# power_input.net
KiCad netlist of a schematic drawn in Altium Designer
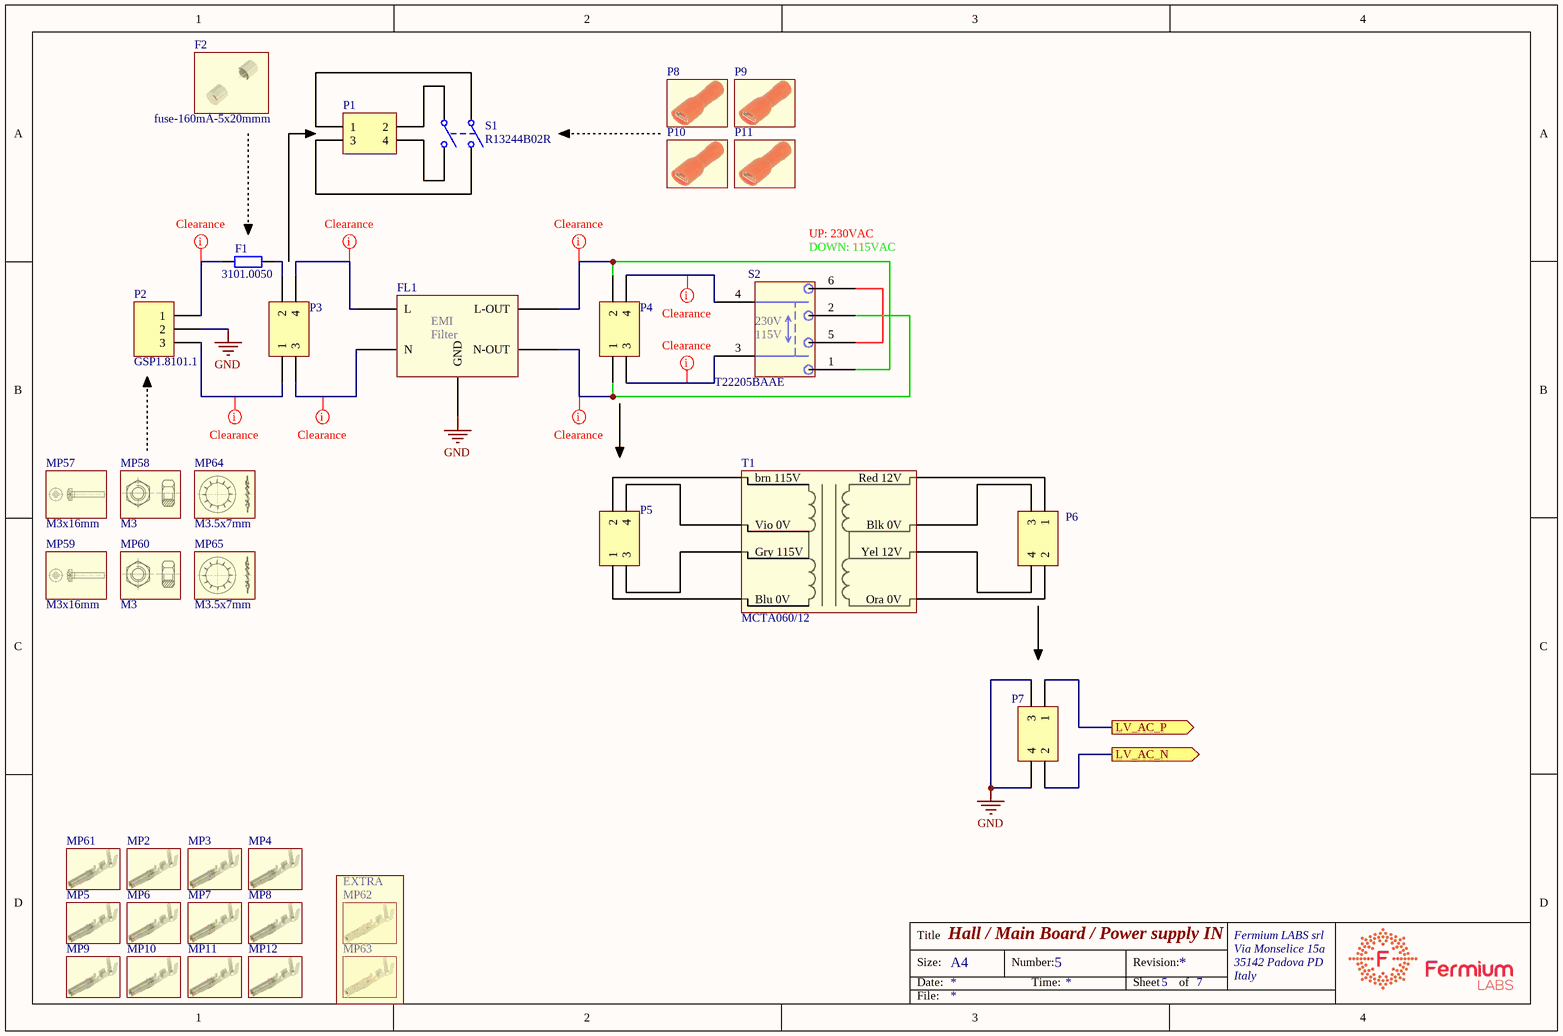
[diagram p0: power_input.SchDoc]

(export (version "E")
  (design (tool "Eeschema 10.0.6"))
  (components
    (comp (ref "F1")
      (value "~")
      (footprint "custom_components:FPG5-3101-0050")
      (description "fuse holder")
      (fields
        (field (name "SUPPLIER PART NUMBER 1") "3101.0050")
        (field (name "MANUFACTURER") "SCHURTER")
        (field (name "MANUFACTURER PART NUMBER") "3101.0050")
      )
      (libsource (lib "Miscellaneous Devices") (part "Res2"))
    )
    (comp (ref "F2")
      (value "fuse-160mA-5x20mmm")
      (fields (field (name "MANUFACTURER PART NUMBER") "522.509") (field (name "MANUFACTURER") "ESKA"))
      (libsource (lib "custom_components") (part "fuse-160mA-5x20mmm"))
    )
    (comp (ref "FL1")
      (value "~")
      (footprint "FM412-2")
      (fields (field (name "MANUFACTURER") "FILTERCON") (field (name "MANUFACTURER PART NUMBER") "FM414-2"))
      (libsource (lib "custom_components") (part "emi_filter"))
    )
    (comp (ref "MP2")
      (value "~")
      (fields (field (name "MANUFACTURER PART NUMBER") "039000060") (field (name "MANUFACTURER") "Molex"))
      (libsource (lib "custom_components") (part "molex-039000060"))
    )
    (comp (ref "MP3")
      (value "~")
      (fields (field (name "MANUFACTURER PART NUMBER") "039000060") (field (name "MANUFACTURER") "Molex"))
      (libsource (lib "custom_components") (part "molex-039000060"))
    )
    (comp (ref "MP4")
      (value "~")
      (fields (field (name "MANUFACTURER PART NUMBER") "039000060") (field (name "MANUFACTURER") "Molex"))
      (libsource (lib "custom_components") (part "molex-039000060"))
    )
    (comp (ref "MP5")
      (value "~")
      (fields (field (name "MANUFACTURER PART NUMBER") "039000060") (field (name "MANUFACTURER") "Molex"))
      (libsource (lib "custom_components") (part "molex-039000060"))
    )
    (comp (ref "MP6")
      (value "~")
      (fields (field (name "MANUFACTURER PART NUMBER") "039000060") (field (name "MANUFACTURER") "Molex"))
      (libsource (lib "custom_components") (part "molex-039000060"))
    )
    (comp (ref "MP7")
      (value "~")
      (fields (field (name "MANUFACTURER PART NUMBER") "039000060") (field (name "MANUFACTURER") "Molex"))
      (libsource (lib "custom_components") (part "molex-039000060"))
    )
    (comp (ref "MP8")
      (value "~")
      (fields (field (name "MANUFACTURER PART NUMBER") "039000060") (field (name "MANUFACTURER") "Molex"))
      (libsource (lib "custom_components") (part "molex-039000060"))
    )
    (comp (ref "MP9")
      (value "~")
      (fields (field (name "MANUFACTURER PART NUMBER") "039000060") (field (name "MANUFACTURER") "Molex"))
      (libsource (lib "custom_components") (part "molex-039000060"))
    )
    (comp (ref "MP10")
      (value "~")
      (fields (field (name "MANUFACTURER PART NUMBER") "039000060") (field (name "MANUFACTURER") "Molex"))
      (libsource (lib "custom_components") (part "molex-039000060"))
    )
    (comp (ref "MP11")
      (value "~")
      (fields (field (name "MANUFACTURER PART NUMBER") "039000060") (field (name "MANUFACTURER") "Molex"))
      (libsource (lib "custom_components") (part "molex-039000060"))
    )
    (comp (ref "MP12")
      (value "~")
      (fields (field (name "MANUFACTURER PART NUMBER") "039000060") (field (name "MANUFACTURER") "Molex"))
      (libsource (lib "custom_components") (part "molex-039000060"))
    )
    (comp (ref "MP57")
      (value "screw-M3x25mm")
      (fields
        (field (name "MANUFACTURER PART NUMBER") "M3X16/D7985")
        (field (name "MANUFACTURER") "KRAFTBERG")
        (field (name "SIZE") "M3x16mm")
      )
      (libsource (lib "custom_components") (part "screw-M3x25mm"))
    )
    (comp (ref "MP58")
      (value "nut-M3")
      (fields
        (field (name "MANUFACTURER PART NUMBER") "1874659")
        (field (name "MANUFACTURER") "BOSSARD")
        (field (name "SIZE") "M3")
      )
      (libsource (lib "custom_components") (part "nut-M3"))
    )
    (comp (ref "MP59")
      (value "screw-M3x25mm")
      (fields
        (field (name "MANUFACTURER PART NUMBER") "M3X16/D7985")
        (field (name "MANUFACTURER") "KRAFTBERG")
        (field (name "SIZE") "M3x16mm")
      )
      (libsource (lib "custom_components") (part "screw-M3x25mm"))
    )
    (comp (ref "MP60")
      (value "nut-M3")
      (fields
        (field (name "MANUFACTURER PART NUMBER") "1874659")
        (field (name "MANUFACTURER") "BOSSARD")
        (field (name "SIZE") "M3")
      )
      (libsource (lib "custom_components") (part "nut-M3"))
    )
    (comp (ref "MP61")
      (value "~")
      (fields (field (name "MANUFACTURER PART NUMBER") "039000060") (field (name "MANUFACTURER") "Molex"))
      (libsource (lib "custom_components") (part "molex-039000060"))
    )
    (comp (ref "MP62")
      (value "~")
      (fields (field (name "MANUFACTURER PART NUMBER") "039000060") (field (name "MANUFACTURER") "Molex"))
      (libsource (lib "custom_components") (part "molex-039000060"))
    )
    (comp (ref "MP63")
      (value "~")
      (fields (field (name "MANUFACTURER PART NUMBER") "039000060") (field (name "MANUFACTURER") "Molex"))
      (libsource (lib "custom_components") (part "molex-039000060"))
    )
    (comp (ref "MP64")
      (value "rondella-dentata-m3.5_1")
      (fields
        (field (name "MANUFACTURER PART NUMBER") "M3.5/BN782 DIN6798J")
        (field (name "MANUFACTURER") "BOSSARD")
        (field (name "SIZE") "M3.5x7mm")
      )
      (libsource (lib "custom_components") (part "rondella-dentata-m3.5_1"))
    )
    (comp (ref "MP65")
      (value "rondella-dentata-m3.5_1")
      (fields
        (field (name "MANUFACTURER PART NUMBER") "M3.5/BN782 DIN6798J")
        (field (name "MANUFACTURER") "BOSSARD")
        (field (name "SIZE") "M3.5x7mm")
      )
      (libsource (lib "custom_components") (part "rondella-dentata-m3.5_1"))
    )
    (comp (ref "P1")
      (value "~")
      (description "connector 4 pin wire")
      (fields (field (name "MANUFACTURER PART NUMBER") "039012040") (field (name "MANUFACTURER") "Molex"))
      (libsource (lib "") (part "Header 2X2_2"))
    )
    (comp (ref "P2")
      (value "~")
      (footprint "custom_components:gsp1-8101-1")
      (description "IEC pcb AC power socket")
      (fields
        (field (name "SUPPLIER PART NUMBER 1") "GSP1.8101.1")
        (field (name "MANUFACTURER") "SCHURTER")
        (field (name "MANUFACTURER PART NUMBER") "GSP1.8101.1")
        (field (name "PUBLISHER") "Altium Limited")
      )
      (libsource (lib "Miscellaneous Connectors") (part "Header 3"))
    )
    (comp (ref "P3")
      (value "~")
      (footprint "molex-039281043")
      (description "Connector 4 wire pcb")
      (fields (field (name "MANUFACTURER PART NUMBER") "039281043") (field (name "MANUFACTURER") "Molex"))
      (libsource (lib "Miscellaneous Connectors") (part "Header 2X2"))
    )
    (comp (ref "P4")
      (value "~")
      (footprint "molex-039281043")
      (description "Connector 4 wire pcb")
      (fields (field (name "MANUFACTURER PART NUMBER") "039281043") (field (name "MANUFACTURER") "Molex"))
      (libsource (lib "Miscellaneous Connectors") (part "Header 2X2"))
    )
    (comp (ref "P5")
      (value "~")
      (description "connector 4 pin wire")
      (fields (field (name "MANUFACTURER PART NUMBER") "039012040") (field (name "MANUFACTURER") "Molex"))
      (libsource (lib "Miscellaneous Connectors") (part "Header 2X2"))
    )
    (comp (ref "P6")
      (value "~")
      (description "connector 4 pin wire")
      (fields (field (name "MANUFACTURER PART NUMBER") "039012040") (field (name "MANUFACTURER") "Molex"))
      (libsource (lib "") (part "Header 2X2_1"))
    )
    (comp (ref "P7")
      (value "~")
      (footprint "molex-039281043")
      (description "Connector 4 wire pcb")
      (fields (field (name "MANUFACTURER PART NUMBER") "039281043") (field (name "MANUFACTURER") "Molex"))
      (libsource (lib "") (part "Header 2X2_1"))
    )
    (comp (ref "P8")
      (value "faston-4.5-f-red")
      (fields (field (name "MANUFACTURER PART NUMBER") "BM 00192") (field (name "MANUFACTURER") "BM GROUP"))
      (libsource (lib "custom_components") (part "faston-4.5-f-red"))
    )
    (comp (ref "P9")
      (value "faston-4.5-f-red")
      (fields (field (name "MANUFACTURER PART NUMBER") "BM 00192") (field (name "MANUFACTURER") "BM GROUP"))
      (libsource (lib "custom_components") (part "faston-4.5-f-red"))
    )
    (comp (ref "P10")
      (value "faston-4.5-f-red")
      (fields (field (name "MANUFACTURER PART NUMBER") "BM 00192") (field (name "MANUFACTURER") "BM GROUP"))
      (libsource (lib "custom_components") (part "faston-4.5-f-red"))
    )
    (comp (ref "P11")
      (value "faston-4.5-f-red")
      (fields (field (name "MANUFACTURER PART NUMBER") "BM 00192") (field (name "MANUFACTURER") "BM GROUP"))
      (libsource (lib "custom_components") (part "faston-4.5-f-red"))
    )
    (comp (ref "S1")
      (value "~")
      (footprint "custom_components:rocker-switch")
      (description "Double-Pole, Single-Throw Switch")
      (fields
        (field (name "SUPPLIER PART NUMBER 1") "R13244B02R")
        (field (name "MANUFACTURER") "SCI")
        (field (name "MANUFACTURER PART NUMBER") "R13-244B-02-BR-2D")
        (field (name "PUBLISHER") "Altium Limited")
      )
      (libsource (lib "Miscellaneous Devices") (part "SW-DPST"))
    )
    (comp (ref "S2")
      (value "~")
      (footprint "custom_components:T22205B")
      (description "Switch DPDT 230-115V")
      (libsource (lib "custom_components") (part "t22205b"))
    )
    (comp (ref "T1")
      (value "toroidal_transformer")
      (footprint "custom_components:MCTA060")
      (fields
        (field (name "MANUFACTURER") "MULTICOMP")
        (field (name "MANUFACTURER PART NUMBER") "MCTA060/12")
      )
      (libsource (lib "custom_components") (part "toroidal_transformer"))
    )
  )
  (nets
    (net (code "1") (name "/LV_AC_N") (class "Default")
      (node (ref "P7") (pin "2") (pinfunction "2_2") (pintype "passive"))
    )
    (net (code "2") (name "/LV_AC_P") (class "Default")
      (node (ref "P7") (pin "1") (pinfunction "1_1") (pintype "passive"))
    )
    (net (code "3") (name "GND") (class "Default")
      (node (ref "FL1") (pin "3") (pinfunction "GND_3") (pintype "passive"))
      (node (ref "P2") (pin "2") (pinfunction "2_2") (pintype "passive"))
      (node (ref "P7") (pin "3") (pinfunction "3_3") (pintype "passive"))
      (node (ref "P7") (pin "4") (pinfunction "4_4") (pintype "passive"))
    )
    (net (code "4") (name "Net-(F1-Pad1)") (class "Default")
      (node (ref "F1") (pin "1") (pinfunction "1_1") (pintype "passive"))
      (node (ref "P2") (pin "1") (pinfunction "1_1") (pintype "passive"))
    )
    (net (code "5") (name "Net-(F1-Pad2)") (class "Default")
      (node (ref "F1") (pin "2") (pinfunction "2_2") (pintype "passive"))
      (node (ref "P3") (pin "2") (pinfunction "2_2") (pintype "passive"))
    )
    (net (code "6") (name "Net-(FL1-L)") (class "Default")
      (node (ref "FL1") (pin "5") (pinfunction "L_5") (pintype "passive"))
      (node (ref "P3") (pin "4") (pinfunction "4_4") (pintype "passive"))
    )
    (net (code "7") (name "Net-(FL1-L-OUT)") (class "Default")
      (node (ref "FL1") (pin "4") (pinfunction "L-OUT_4") (pintype "passive"))
      (node (ref "P4") (pin "2") (pinfunction "2_2") (pintype "passive"))
      (node (ref "S2") (pin "1") (pinfunction "1_1") (pintype "passive"))
    )
    (net (code "8") (name "Net-(FL1-N)") (class "Default")
      (node (ref "FL1") (pin "1") (pinfunction "N_1") (pintype "passive"))
      (node (ref "P3") (pin "3") (pinfunction "3_3") (pintype "passive"))
    )
    (net (code "9") (name "Net-(FL1-N-OUT)") (class "Default")
      (node (ref "FL1") (pin "2") (pinfunction "N-OUT_2") (pintype "passive"))
      (node (ref "P4") (pin "1") (pinfunction "1_1") (pintype "passive"))
      (node (ref "S2") (pin "2") (pinfunction "2_2") (pintype "passive"))
    )
    (net (code "10") (name "Net-(P2-Pad3)") (class "Default")
      (node (ref "P2") (pin "3") (pinfunction "3_3") (pintype "passive"))
      (node (ref "P3") (pin "1") (pinfunction "1_1") (pintype "passive"))
    )
    (net (code "11") (name "Net-(P4-Pad3)") (class "Default")
      (node (ref "P4") (pin "3") (pinfunction "3_3") (pintype "passive"))
      (node (ref "S2") (pin "3") (pinfunction "3_3") (pintype "passive"))
    )
    (net (code "12") (name "Net-(P4-Pad4)") (class "Default")
      (node (ref "P4") (pin "4") (pinfunction "4_4") (pintype "passive"))
      (node (ref "S2") (pin "4") (pinfunction "4_4") (pintype "passive"))
    )
    (net (code "13") (name "Net-(S2-Pad5)") (class "Default")
      (node (ref "S2") (pin "5") (pinfunction "5_5") (pintype "passive"))
      (node (ref "S2") (pin "6") (pinfunction "6_6") (pintype "passive"))
    )
    (net (code "14") (name "unconnected-(P1-Pad1)") (class "Default")
      (node (ref "P1") (pin "1") (pinfunction "1_1") (pintype "passive"))
    )
    (net (code "15") (name "unconnected-(P1-Pad2)") (class "Default")
      (node (ref "P1") (pin "2") (pinfunction "2_2") (pintype "passive"))
    )
    (net (code "16") (name "unconnected-(P1-Pad3)") (class "Default")
      (node (ref "P1") (pin "3") (pinfunction "3_3") (pintype "passive"))
    )
    (net (code "17") (name "unconnected-(P1-Pad4)") (class "Default")
      (node (ref "P1") (pin "4") (pinfunction "4_4") (pintype "passive"))
    )
    (net (code "18") (name "unconnected-(P5-Pad1)") (class "Default")
      (node (ref "P5") (pin "1") (pinfunction "1_1") (pintype "passive"))
    )
    (net (code "19") (name "unconnected-(P5-Pad2)") (class "Default")
      (node (ref "P5") (pin "2") (pinfunction "2_2") (pintype "passive"))
    )
    (net (code "20") (name "unconnected-(P5-Pad3)") (class "Default")
      (node (ref "P5") (pin "3") (pinfunction "3_3") (pintype "passive"))
    )
    (net (code "21") (name "unconnected-(P5-Pad4)") (class "Default")
      (node (ref "P5") (pin "4") (pinfunction "4_4") (pintype "passive"))
    )
    (net (code "22") (name "unconnected-(P6-Pad1)") (class "Default")
      (node (ref "P6") (pin "1") (pinfunction "1_1") (pintype "passive"))
    )
    (net (code "23") (name "unconnected-(P6-Pad2)") (class "Default")
      (node (ref "P6") (pin "2") (pinfunction "2_2") (pintype "passive"))
    )
    (net (code "24") (name "unconnected-(P6-Pad3)") (class "Default")
      (node (ref "P6") (pin "3") (pinfunction "3_3") (pintype "passive"))
    )
    (net (code "25") (name "unconnected-(P6-Pad4)") (class "Default")
      (node (ref "P6") (pin "4") (pinfunction "4_4") (pintype "passive"))
    )
    (net (code "26") (name "unconnected-(S1-COMMON1-Pad1)") (class "Default")
      (node (ref "S1") (pin "1") (pinfunction "COMMON1_1") (pintype "passive"))
    )
    (net (code "27") (name "unconnected-(S1-COMMON2-Pad3)") (class "Default")
      (node (ref "S1") (pin "3") (pinfunction "COMMON2_3") (pintype "passive"))
    )
    (net (code "28") (name "unconnected-(S1-NO1-Pad2)") (class "Default")
      (node (ref "S1") (pin "2") (pinfunction "NO1_2") (pintype "passive"))
    )
    (net (code "29") (name "unconnected-(S1-NO2-Pad4)") (class "Default")
      (node (ref "S1") (pin "4") (pinfunction "NO2_4") (pintype "passive"))
    )
    (net (code "30") (name "unconnected-(T1-Blk_0V-Pad7)") (class "Default")
      (node (ref "T1") (pin "7") (pinfunction "Blk_0V_7") (pintype "passive"))
    )
    (net (code "31") (name "unconnected-(T1-Blu_0V-Pad4)") (class "Default")
      (node (ref "T1") (pin "4") (pinfunction "Blu_0V_4") (pintype "passive"))
    )
    (net (code "32") (name "unconnected-(T1-Gry_115V-Pad3)") (class "Default")
      (node (ref "T1") (pin "3") (pinfunction "Gry_115V_3") (pintype "passive"))
    )
    (net (code "33") (name "unconnected-(T1-Ora_0V-Pad5)") (class "Default")
      (node (ref "T1") (pin "5") (pinfunction "Ora_0V_5") (pintype "passive"))
    )
    (net (code "34") (name "unconnected-(T1-Red_12V-Pad8)") (class "Default")
      (node (ref "T1") (pin "8") (pinfunction "Red_12V_8") (pintype "passive"))
    )
    (net (code "35") (name "unconnected-(T1-Vio_0V-Pad2)") (class "Default")
      (node (ref "T1") (pin "2") (pinfunction "Vio_0V_2") (pintype "passive"))
    )
    (net (code "36") (name "unconnected-(T1-Yel_12V-Pad6)") (class "Default")
      (node (ref "T1") (pin "6") (pinfunction "Yel_12V_6") (pintype "passive"))
    )
    (net (code "37") (name "unconnected-(T1-brn_115V-Pad1)") (class "Default")
      (node (ref "T1") (pin "1") (pinfunction "brn_115V_1") (pintype "passive"))
    )
  )
)
